# FridgeWarninig_0_1.net
KiCad netlist of a schematic drawn in EAGLE
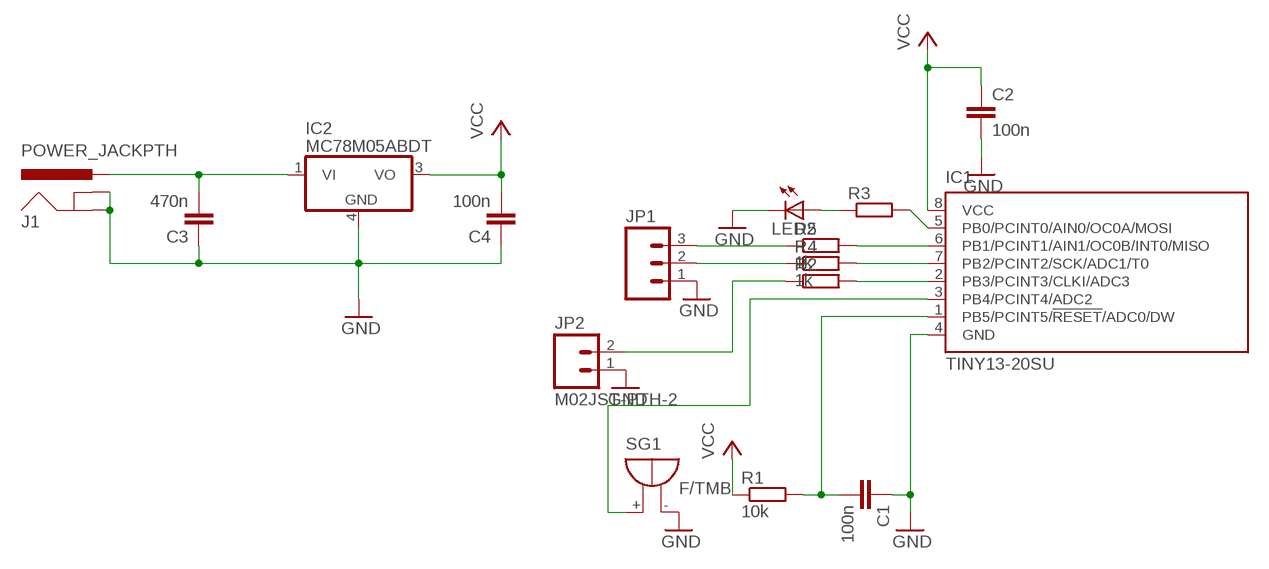
[diagram p0: schematic, sheet 1]

(export (version "E")
  (design (tool "Eeschema 10.0.6"))
  (components
    (comp (ref "C1")
      (value "100n")
      (footprint "eagle-import:C0805")
      (libsource (lib "eagle-import") (part "C-EUC0805"))
    )
    (comp (ref "C2")
      (value "100n")
      (footprint "eagle-import:C0805")
      (libsource (lib "eagle-import") (part "C-EUC0805"))
    )
    (comp (ref "C3")
      (value "470n")
      (footprint "eagle-import:C0805")
      (libsource (lib "eagle-import") (part "C-EUC0805"))
    )
    (comp (ref "C4")
      (value "100n")
      (footprint "eagle-import:C0805")
      (libsource (lib "eagle-import") (part "C-EUC0805"))
    )
    (comp (ref "IC1")
      (value "TINY13-20SU")
      (footprint "eagle-import:8S2")
      (fields (field (name "MPN") "ATTINY13-20SU"))
      (libsource (lib "eagle-import") (part "TINY13SU-20"))
    )
    (comp (ref "IC2")
      (value "MC78M05ABDT")
      (footprint "eagle-import:DPACK_3")
      (libsource (lib "eagle-import") (part "MC78M05ABDT"))
    )
    (comp (ref "J1")
      (value "POWER_JACKPTH")
      (footprint "eagle-import:POWER_JACK_PTH")
      (libsource (lib "eagle-import") (part "POWER_JACKPTH"))
    )
    (comp (ref "JP1")
      (value "M03JST-PTH")
      (footprint "eagle-import:JST-3-PTH")
      (libsource (lib "eagle-import") (part "M03JST-PTH"))
    )
    (comp (ref "JP2")
      (value "M02JST-PTH-2")
      (footprint "eagle-import:JST-2-PTH")
      (libsource (lib "eagle-import") (part "M02JST-PTH-2"))
    )
    (comp (ref "LED2")
      (value "LEDCHIP-LED0603")
      (footprint "eagle-import:CHIP-LED0603")
      (libsource (lib "eagle-import") (part "LEDCHIP-LED0603"))
    )
    (comp (ref "R1")
      (value "10k")
      (footprint "eagle-import:R0805")
      (libsource (lib "eagle-import") (part "R-EU_R0805"))
    )
    (comp (ref "R2")
      (value "R-EU_R0805")
      (footprint "eagle-import:R0805")
      (libsource (lib "eagle-import") (part "R-EU_R0805"))
    )
    (comp (ref "R3")
      (value "R-EU_R0603")
      (footprint "eagle-import:R0603")
      (libsource (lib "eagle-import") (part "R-EU_R0603"))
    )
    (comp (ref "R4")
      (value "1k")
      (footprint "eagle-import:R0805")
      (libsource (lib "eagle-import") (part "R-EU_R0805"))
    )
    (comp (ref "R5")
      (value "1k")
      (footprint "eagle-import:R0805")
      (libsource (lib "eagle-import") (part "R-EU_R0805"))
    )
    (comp (ref "SG1")
      (value "F/TMB")
      (footprint "eagle-import:F_TMB")
      (libsource (lib "eagle-import") (part "F/TMB"))
    )
  )
  (nets
    (net (code "1") (name "GND") (class "Default")
      (node (ref "C1") (pin "1") (pinfunction "1_1") (pintype "passive"))
      (node (ref "C2") (pin "2") (pinfunction "2_2") (pintype "passive"))
      (node (ref "C3") (pin "1") (pinfunction "1_1") (pintype "passive"))
      (node (ref "C4") (pin "1") (pinfunction "1_1") (pintype "passive"))
      (node (ref "IC1") (pin "4") (pinfunction "GND_4") (pintype "power_in"))
      (node (ref "IC2") (pin "4") (pinfunction "GND_4") (pintype "passive"))
      (node (ref "J1") (pin "GND") (pinfunction "GND_GND") (pintype "bidirectional"))
      (node (ref "J1") (pin "GNDBREAK") (pinfunction "GNDBREAK_GNDBREAK") (pintype "bidirectional"))
      (node (ref "JP1") (pin "1") (pinfunction "1_1") (pintype "passive"))
      (node (ref "JP2") (pin "1") (pinfunction "1_1") (pintype "passive"))
      (node (ref "LED2") (pin "C") (pinfunction "C_C") (pintype "passive"))
      (node (ref "SG1") (pin "-") (pinfunction "-_-") (pintype "passive"))
    )
    (net (code "2") (name "Net-(IC1-PB0{slash}PCINT0{slash}AIN0{slash}OC0A{slash}MOSI)") (class "Default")
      (node (ref "IC1") (pin "5") (pinfunction "PB0/PCINT0/AIN0/OC0A/MOSI_5") (pintype "bidirectional"))
      (node (ref "R3") (pin "2") (pinfunction "2_2") (pintype "passive"))
    )
    (net (code "3") (name "Net-(IC1-PB1{slash}PCINT1{slash}AIN1{slash}OC0B{slash}INT0{slash}MISO)") (class "Default")
      (node (ref "IC1") (pin "6") (pinfunction "PB1/PCINT1/AIN1/OC0B/INT0/MISO_6") (pintype "bidirectional"))
      (node (ref "R5") (pin "2") (pinfunction "2_2") (pintype "passive"))
    )
    (net (code "4") (name "Net-(IC1-PB2{slash}PCINT2{slash}SCK{slash}ADC1{slash}T0)") (class "Default")
      (node (ref "IC1") (pin "7") (pinfunction "PB2/PCINT2/SCK/ADC1/T0_7") (pintype "bidirectional"))
      (node (ref "R4") (pin "2") (pinfunction "2_2") (pintype "passive"))
    )
    (net (code "5") (name "Net-(IC1-PB3{slash}PCINT3{slash}CLKI{slash}ADC3)") (class "Default")
      (node (ref "IC1") (pin "2") (pinfunction "PB3/PCINT3/CLKI/ADC3_2") (pintype "bidirectional"))
      (node (ref "R2") (pin "2") (pinfunction "2_2") (pintype "passive"))
    )
    (net (code "6") (name "Net-(IC1-PB4{slash}PCINT4{slash}ADC2)") (class "Default")
      (node (ref "IC1") (pin "3") (pinfunction "PB4/PCINT4/ADC2_3") (pintype "bidirectional"))
      (node (ref "SG1") (pin "+") (pinfunction "+_+") (pintype "passive"))
    )
    (net (code "7") (name "Net-(IC1-PB5{slash}PCINT5{slash}~{RESET}{slash}ADC0{slash}DW)") (class "Default")
      (node (ref "C1") (pin "2") (pinfunction "2_2") (pintype "passive"))
      (node (ref "IC1") (pin "1") (pinfunction "PB5/PCINT5/~{RESET}/ADC0/DW_1") (pintype "bidirectional"))
      (node (ref "R1") (pin "2") (pinfunction "2_2") (pintype "passive"))
    )
    (net (code "8") (name "Net-(IC2-VI)") (class "Default")
      (node (ref "C3") (pin "2") (pinfunction "2_2") (pintype "passive"))
      (node (ref "IC2") (pin "1") (pinfunction "VI_1") (pintype "input"))
      (node (ref "J1") (pin "PWR") (pinfunction "PWR_PWR") (pintype "bidirectional"))
    )
    (net (code "9") (name "Net-(JP1-Pad2)") (class "Default")
      (node (ref "JP1") (pin "2") (pinfunction "2_2") (pintype "passive"))
      (node (ref "R4") (pin "1") (pinfunction "1_1") (pintype "passive"))
    )
    (net (code "10") (name "Net-(JP1-Pad3)") (class "Default")
      (node (ref "JP1") (pin "3") (pinfunction "3_3") (pintype "passive"))
      (node (ref "R5") (pin "1") (pinfunction "1_1") (pintype "passive"))
    )
    (net (code "11") (name "Net-(JP2-Pad2)") (class "Default")
      (node (ref "JP2") (pin "2") (pinfunction "2_2") (pintype "passive"))
      (node (ref "R2") (pin "1") (pinfunction "1_1") (pintype "passive"))
    )
    (net (code "12") (name "Net-(LED2-PadA)") (class "Default")
      (node (ref "LED2") (pin "A") (pinfunction "A_A") (pintype "passive"))
      (node (ref "R3") (pin "1") (pinfunction "1_1") (pintype "passive"))
    )
    (net (code "13") (name "VCC") (class "Default")
      (node (ref "C2") (pin "1") (pinfunction "1_1") (pintype "passive"))
      (node (ref "C4") (pin "2") (pinfunction "2_2") (pintype "passive"))
      (node (ref "IC1") (pin "8") (pinfunction "VCC_8") (pintype "power_in"))
      (node (ref "IC2") (pin "3") (pinfunction "VO_3") (pintype "passive"))
      (node (ref "R1") (pin "1") (pinfunction "1_1") (pintype "passive"))
    )
  )
)
